# Sheet1.net
KiCad netlist of a schematic drawn in Altium Designer
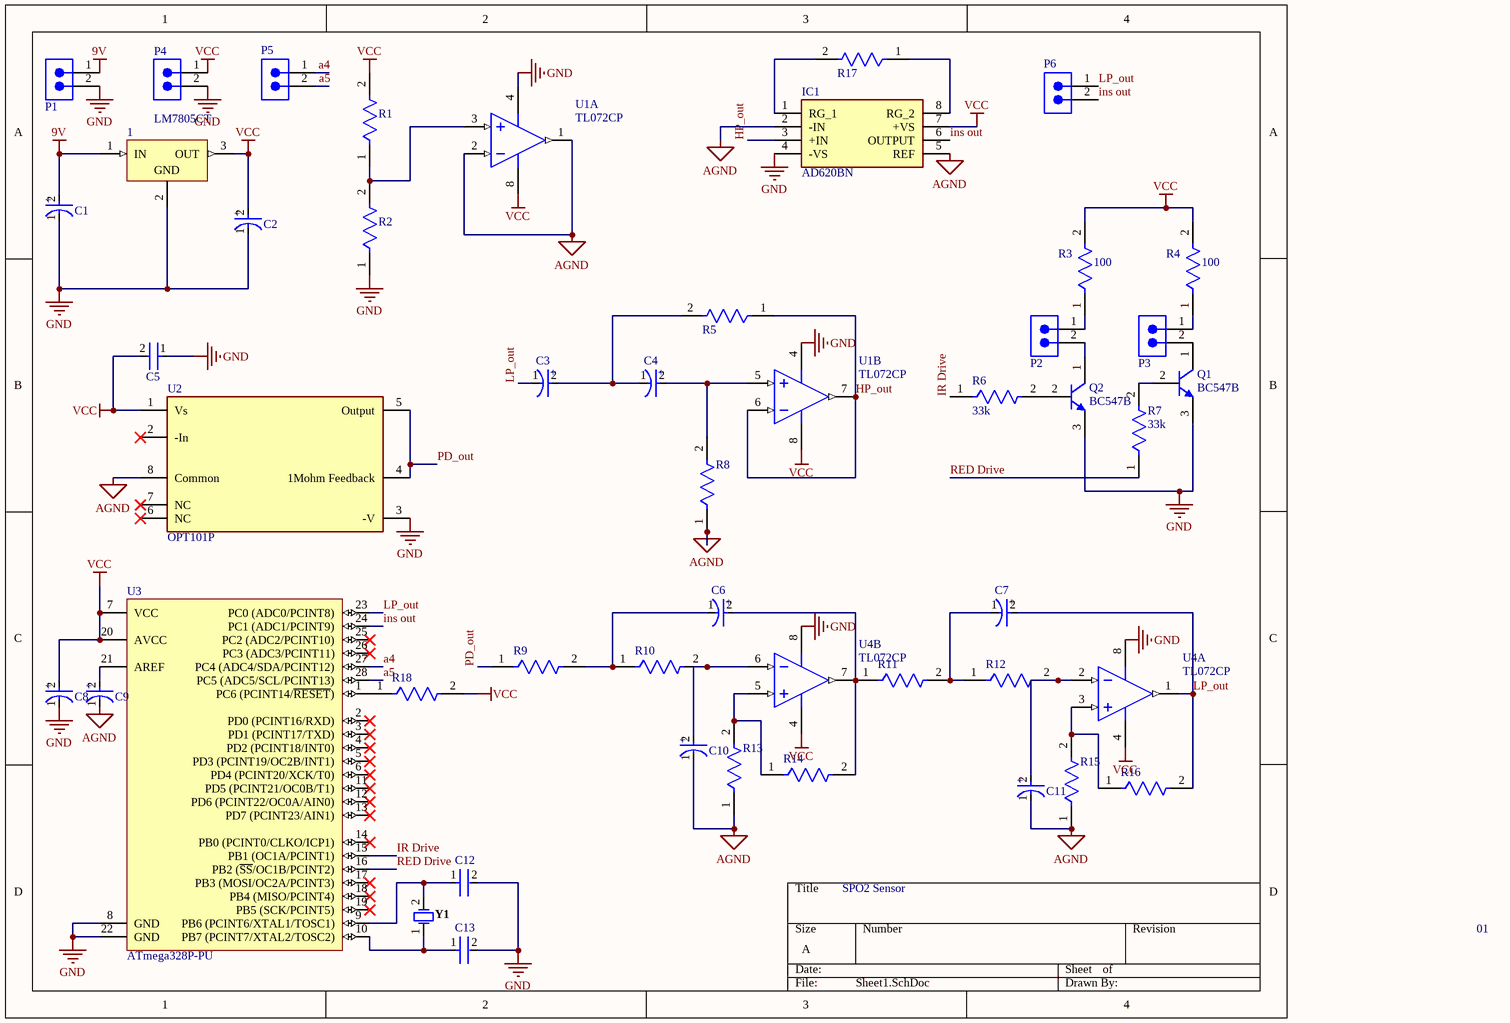
[diagram p0: Sheet1.SchDoc]

(export (version "E")
  (design (tool "Eeschema 10.0.6"))
  (components
    (comp (ref "1")
      (value "LM7805CT")
      (footprint "FAIR-TO-220-3")
      (description "Fixed Positive Standard Regulator, 5VBIPolar, PSFM3")
      (libsource (lib "herathhmsi 21") (part "FAIR-LM7805CT-TO220-3"))
    )
    (comp (ref "C1")
      (value "EEUFC1H150")
      (footprint "FP-RAD-TH-D_5_0_5-L_11_1-MFG")
      (description "Aluminum Electrolytic Capacitors (Radial Lead Type) AEC-Q200 Qualified 15uF ±20% 50V")
      (fields (field (name "TOLERANCE") "20%") (field (name "VOLTAGE") "50V"))
      (libsource (lib "Altium Content Vault") (part "a00bbbee19879c290e62620ae7e47b1"))
    )
    (comp (ref "C2")
      (value "EEUFC1H150")
      (footprint "FP-RAD-TH-D_5_0_5-L_11_1-MFG")
      (description "Aluminum Electrolytic Capacitors (Radial Lead Type) AEC-Q200 Qualified 15uF ±20% 50V")
      (fields (field (name "TOLERANCE") "20%") (field (name "VOLTAGE") "50V"))
      (libsource (lib "Altium Content Vault") (part "a00bbbee19879c290e62620ae7e47b1"))
    )
    (comp (ref "C3")
      (value "EEUFC1H150")
      (footprint "FP-RAD-TH-D_5_0_5-L_11_1-MFG")
      (description "Aluminum Electrolytic Capacitors (Radial Lead Type) AEC-Q200 Qualified 15uF ±20% 50V")
      (fields (field (name "TOLERANCE") "20%") (field (name "VOLTAGE") "50V"))
      (libsource (lib "Altium Content Vault") (part "a00bbbee19879c290e62620ae7e47b1"))
    )
    (comp (ref "C4")
      (value "EEUFC1H150")
      (footprint "FP-RAD-TH-D_5_0_5-L_11_1-MFG")
      (description "Aluminum Electrolytic Capacitors (Radial Lead Type) AEC-Q200 Qualified 15uF ±20% 50V")
      (fields (field (name "TOLERANCE") "20%") (field (name "VOLTAGE") "50V"))
      (libsource (lib "Altium Content Vault") (part "a00bbbee19879c290e62620ae7e47b1"))
    )
    (comp (ref "C5")
      (value "RCER72A104K1DBH03A")
      (footprint "FP-RCE1A2-MFG")
      (description "Cap Ceramic 100nF 100V X7R ±10% Radial 2.5mm +125°C Automotive Ammo Pack")
      (fields (field (name "TOLERANCE") "10%"))
      (libsource (lib "Altium Content Vault") (part "02cd4be3c70576c341d710602a673aa"))
    )
    (comp (ref "C6")
      (value "EEUFC1H150")
      (footprint "FP-RAD-TH-D_5_0_5-L_11_1-MFG")
      (description "Aluminum Electrolytic Capacitors (Radial Lead Type) AEC-Q200 Qualified 15uF ±20% 50V")
      (fields (field (name "TOLERANCE") "20%") (field (name "VOLTAGE") "50V"))
      (libsource (lib "Altium Content Vault") (part "a00bbbee19879c290e62620ae7e47b1"))
    )
    (comp (ref "C7")
      (value "EEUFC1H150")
      (footprint "FP-RAD-TH-D_5_0_5-L_11_1-MFG")
      (description "Aluminum Electrolytic Capacitors (Radial Lead Type) AEC-Q200 Qualified 15uF ±20% 50V")
      (fields (field (name "TOLERANCE") "20%") (field (name "VOLTAGE") "50V"))
      (libsource (lib "Altium Content Vault") (part "a00bbbee19879c290e62620ae7e47b1"))
    )
    (comp (ref "C8")
      (value "EEUFC1H150")
      (footprint "FP-RAD-TH-D_5_0_5-L_11_1-MFG")
      (description "Aluminum Electrolytic Capacitors (Radial Lead Type) AEC-Q200 Qualified 15uF ±20% 50V")
      (fields (field (name "TOLERANCE") "20%") (field (name "VOLTAGE") "50V"))
      (libsource (lib "Altium Content Vault") (part "a00bbbee19879c290e62620ae7e47b1"))
    )
    (comp (ref "C9")
      (value "EEUFC1H150")
      (footprint "FP-RAD-TH-D_5_0_5-L_11_1-MFG")
      (description "Aluminum Electrolytic Capacitors (Radial Lead Type) AEC-Q200 Qualified 15uF ±20% 50V")
      (fields (field (name "TOLERANCE") "20%") (field (name "VOLTAGE") "50V"))
      (libsource (lib "Altium Content Vault") (part "a00bbbee19879c290e62620ae7e47b1"))
    )
    (comp (ref "C10")
      (value "EEUFC1H150")
      (footprint "FP-RAD-TH-D_5_0_5-L_11_1-MFG")
      (description "Aluminum Electrolytic Capacitors (Radial Lead Type) AEC-Q200 Qualified 15uF ±20% 50V")
      (fields (field (name "TOLERANCE") "20%") (field (name "VOLTAGE") "50V"))
      (libsource (lib "Altium Content Vault") (part "a00bbbee19879c290e62620ae7e47b1"))
    )
    (comp (ref "C11")
      (value "EEUFC1H150")
      (footprint "FP-RAD-TH-D_5_0_5-L_11_1-MFG")
      (description "Aluminum Electrolytic Capacitors (Radial Lead Type) AEC-Q200 Qualified 15uF ±20% 50V")
      (fields (field (name "TOLERANCE") "20%") (field (name "VOLTAGE") "50V"))
      (libsource (lib "Altium Content Vault") (part "a00bbbee19879c290e62620ae7e47b1"))
    )
    (comp (ref "C12")
      (value "RCE5C2A102J0K1H03B")
      (footprint "FP-RCE0K1-MFG")
      (description "Cap Ceramic 1nF 100V C0G ±5% Radial 5mm +125°C Automotive Bulk")
      (fields (field (name "TOLERANCE") "5%"))
      (libsource (lib "Altium Content Vault") (part "b4654b650e69147ec39a6b967a45e02"))
    )
    (comp (ref "C13")
      (value "RCE5C2A102J0K1H03B")
      (footprint "FP-RCE0K1-MFG")
      (description "Cap Ceramic 1nF 100V C0G ±5% Radial 5mm +125°C Automotive Bulk")
      (fields (field (name "TOLERANCE") "5%"))
      (libsource (lib "Altium Content Vault") (part "b4654b650e69147ec39a6b967a45e02"))
    )
    (comp (ref "IC1")
      (value "AD620BN")
      (footprint "DIP794W56P254L959H533Q8N")
      (description "Integrated Circuit")
      (libsource (lib "Schlib1") (part "AD620BN"))
    )
    (comp (ref "P1")
      (value "TSW-102-26-F-S")
      (footprint "SMTC-TSW-102-26-XX-S")
      (description "0.025\" SQ Post Header, Through-hole, Vertical, -55 to 125 degC, 2.54 mm Pitch, 2-Pin, Male, RoHS")
      (fields (field (name "MANUFACTURER") "Samtec"))
      (libsource (lib "Altium Content Vault") (part "SMTC-TSW-102-X-X-S-X"))
    )
    (comp (ref "P2")
      (value "TSW-102-26-F-S")
      (footprint "SMTC-TSW-102-26-XX-S")
      (description "0.025\" SQ Post Header, Through-hole, Vertical, -55 to 125 degC, 2.54 mm Pitch, 2-Pin, Male, RoHS")
      (fields (field (name "MANUFACTURER") "Samtec"))
      (libsource (lib "Altium Content Vault") (part "SMTC-TSW-102-X-X-S-X"))
    )
    (comp (ref "P3")
      (value "TSW-102-26-F-S")
      (footprint "SMTC-TSW-102-26-XX-S")
      (description "0.025\" SQ Post Header, Through-hole, Vertical, -55 to 125 degC, 2.54 mm Pitch, 2-Pin, Male, RoHS")
      (fields (field (name "MANUFACTURER") "Samtec"))
      (libsource (lib "Altium Content Vault") (part "SMTC-TSW-102-X-X-S-X"))
    )
    (comp (ref "P4")
      (value "TSW-102-26-F-S")
      (footprint "SMTC-TSW-102-26-XX-S")
      (description "0.025\" SQ Post Header, Through-hole, Vertical, -55 to 125 degC, 2.54 mm Pitch, 2-Pin, Male, RoHS")
      (fields (field (name "MANUFACTURER") "Samtec"))
      (libsource (lib "Altium Content Vault") (part "SMTC-TSW-102-X-X-S-X"))
    )
    (comp (ref "P5")
      (value "TSW-102-26-F-S")
      (footprint "SMTC-TSW-102-26-XX-S")
      (description "0.025\" SQ Post Header, Through-hole, Vertical, -55 to 125 degC, 2.54 mm Pitch, 2-Pin, Male, RoHS")
      (fields (field (name "MANUFACTURER") "Samtec"))
      (libsource (lib "Altium Content Vault") (part "SMTC-TSW-102-X-X-S-X"))
    )
    (comp (ref "P6")
      (value "TSW-102-26-F-S")
      (footprint "SMTC-TSW-102-26-XX-S")
      (description "0.025\" SQ Post Header, Through-hole, Vertical, -55 to 125 degC, 2.54 mm Pitch, 2-Pin, Male, RoHS")
      (fields (field (name "MANUFACTURER") "Samtec"))
      (libsource (lib "Altium Content Vault") (part "SMTC-TSW-102-X-X-S-X"))
    )
    (comp (ref "Q1")
      (value "BC547B")
      (footprint "ONSC-TO-92-3-29-11")
      (description "Amplifier Transistor, NPN Silicon, 3-Pin TO-92, Bulk Box")
      (fields (field (name "MANUFACTURER") "On Semiconductor"))
      (libsource (lib "Altium Content Vault") (part "ONSC-NPN-C1B2E3-3"))
    )
    (comp (ref "Q2")
      (value "BC547B")
      (footprint "ONSC-TO-92-3-29-11")
      (description "Amplifier Transistor, NPN Silicon, 3-Pin TO-92, Bulk Box")
      (fields (field (name "MANUFACTURER") "On Semiconductor"))
      (libsource (lib "Altium Content Vault") (part "ONSC-NPN-C1B2E3-3"))
    )
    (comp (ref "R1")
      (value "RLR07C1002FSB14")
      (footprint "FP-RLR07-MFG")
      (fields (field (name "TOLERANCE") "1%"))
      (libsource (lib "Altium Content Vault") (part "1029c3af85768c4190bb7ad29bc67b5"))
    )
    (comp (ref "R2")
      (value "RLR07C1002FSB14")
      (footprint "FP-RLR07-MFG")
      (fields (field (name "TOLERANCE") "1%"))
      (libsource (lib "Altium Content Vault") (part "1029c3af85768c4190bb7ad29bc67b5"))
    )
    (comp (ref "R3")
      (value "100")
      (footprint "FP-RLR07-MFG")
      (fields (field (name "TOLERANCE") "1%"))
      (libsource (lib "Altium Content Vault") (part "1029c3af85768c4190bb7ad29bc67b5"))
    )
    (comp (ref "R4")
      (value "100")
      (footprint "FP-RLR07-MFG")
      (fields (field (name "TOLERANCE") "1%"))
      (libsource (lib "Altium Content Vault") (part "1029c3af85768c4190bb7ad29bc67b5"))
    )
    (comp (ref "R5")
      (value "RLR07C1002FSB14")
      (footprint "FP-RLR07-MFG")
      (fields (field (name "TOLERANCE") "1%"))
      (libsource (lib "Altium Content Vault") (part "1029c3af85768c4190bb7ad29bc67b5"))
    )
    (comp (ref "R6")
      (value "33k")
      (footprint "FP-RLR07-MFG")
      (fields (field (name "TOLERANCE") "1%"))
      (libsource (lib "Altium Content Vault") (part "1029c3af85768c4190bb7ad29bc67b5"))
    )
    (comp (ref "R7")
      (value "33k")
      (footprint "FP-RLR07-MFG")
      (fields (field (name "TOLERANCE") "1%"))
      (libsource (lib "Altium Content Vault") (part "1029c3af85768c4190bb7ad29bc67b5"))
    )
    (comp (ref "R8")
      (value "RLR07C1002FSB14")
      (footprint "FP-RLR07-MFG")
      (fields (field (name "TOLERANCE") "1%"))
      (libsource (lib "Altium Content Vault") (part "1029c3af85768c4190bb7ad29bc67b5"))
    )
    (comp (ref "R9")
      (value "RLR07C1002FSB14")
      (footprint "FP-RLR07-MFG")
      (fields (field (name "TOLERANCE") "1%"))
      (libsource (lib "Altium Content Vault") (part "1029c3af85768c4190bb7ad29bc67b5"))
    )
    (comp (ref "R10")
      (value "RLR07C1002FSB14")
      (footprint "FP-RLR07-MFG")
      (fields (field (name "TOLERANCE") "1%"))
      (libsource (lib "Altium Content Vault") (part "1029c3af85768c4190bb7ad29bc67b5"))
    )
    (comp (ref "R11")
      (value "RLR07C1002FSB14")
      (footprint "FP-RLR07-MFG")
      (fields (field (name "TOLERANCE") "1%"))
      (libsource (lib "Altium Content Vault") (part "1029c3af85768c4190bb7ad29bc67b5"))
    )
    (comp (ref "R12")
      (value "RLR07C1002FSB14")
      (footprint "FP-RLR07-MFG")
      (fields (field (name "TOLERANCE") "1%"))
      (libsource (lib "Altium Content Vault") (part "1029c3af85768c4190bb7ad29bc67b5"))
    )
    (comp (ref "R13")
      (value "RLR07C1002FSB14")
      (footprint "FP-RLR07-MFG")
      (fields (field (name "TOLERANCE") "1%"))
      (libsource (lib "Altium Content Vault") (part "1029c3af85768c4190bb7ad29bc67b5"))
    )
    (comp (ref "R14")
      (value "RLR07C1002FSB14")
      (footprint "FP-RLR07-MFG")
      (fields (field (name "TOLERANCE") "1%"))
      (libsource (lib "Altium Content Vault") (part "1029c3af85768c4190bb7ad29bc67b5"))
    )
    (comp (ref "R15")
      (value "RLR07C1002FSB14")
      (footprint "FP-RLR07-MFG")
      (fields (field (name "TOLERANCE") "1%"))
      (libsource (lib "Altium Content Vault") (part "1029c3af85768c4190bb7ad29bc67b5"))
    )
    (comp (ref "R16")
      (value "RLR07C1002FSB14")
      (footprint "FP-RLR07-MFG")
      (fields (field (name "TOLERANCE") "1%"))
      (libsource (lib "Altium Content Vault") (part "1029c3af85768c4190bb7ad29bc67b5"))
    )
    (comp (ref "R17")
      (value "RLR07C1002FSB14")
      (footprint "FP-RLR07-MFG")
      (fields (field (name "TOLERANCE") "1%"))
      (libsource (lib "Altium Content Vault") (part "1029c3af85768c4190bb7ad29bc67b5"))
    )
    (comp (ref "R18")
      (value "RLR07C1002FSB14")
      (footprint "FP-RLR07-MFG")
      (fields (field (name "TOLERANCE") "1%"))
      (libsource (lib "Altium Content Vault") (part "1029c3af85768c4190bb7ad29bc67b5"))
    )
    (comp (ref "U1")
      (value "TL072CP")
      (footprint "P0008A")
      (fields (field (name "MANUFACTURER") "Texas Instruments"))
      (libsource (lib "Altium Content Vault") (part "TI-AMP-D6-2-8_D"))
    )
    (comp (ref "U2")
      (value "OPT101P")
      (footprint "FP-NTC0008A-MFG")
      (description "SENSOR OPT 650NM AMBIENT 8DIP")
      (libsource (lib "Altium Content Vault") (part "30f9e53383154c6943bb97ca6fc90e9"))
    )
    (comp (ref "U3")
      (value "ATmega328P-PU")
      (footprint "28P3")
      (libsource (lib "Altium Content Vault") (part "MC-8B-ATM48-IL28"))
    )
    (comp (ref "U4")
      (value "TL072CP")
      (footprint "P0008A")
      (fields (field (name "MANUFACTURER") "Texas Instruments"))
      (libsource (lib "Altium Content Vault") (part "TI-AMP-D6-2-8_D"))
    )
    (comp (ref "Y1")
      (value "FOXSLF/160-20")
      (footprint "FOX-FOXSLF160-20")
      (description "Resistance Weld Thru-Hole Crystal, 16 MHz, -20 to 70 degC, 2-Pin THD, RoHS, Bulk")
      (fields (field (name "TOLERANCE") "1%"))
      (libsource (lib "Altium Content Vault") (part "XTAL-1-2-2"))
    )
  )
  (nets
    (net (code "1") (name "/HP_out") (class "Default")
      (node (ref "IC1") (pin "3") (pinfunction "+IN_3") (pintype "passive"))
      (node (ref "R5") (pin "1") (pinfunction "1_1") (pintype "passive"))
      (node (ref "U1") (pin "6") (pinfunction "IN2-_6") (pintype "input"))
      (node (ref "U1") (pin "7") (pinfunction "OUT2_7") (pintype "output"))
    )
    (net (code "2") (name "/IR Drive") (class "Default")
      (node (ref "R6") (pin "1") (pinfunction "1_1") (pintype "passive"))
      (node (ref "U3") (pin "15") (pinfunction "PB1_(OC1A/PCINT1)_15") (pintype "bidirectional"))
    )
    (net (code "3") (name "/LP_out") (class "Default")
      (node (ref "C3") (pin "1") (pinfunction "C_1") (pintype "passive"))
      (node (ref "C7") (pin "2") (pinfunction "A_2") (pintype "passive"))
      (node (ref "P6") (pin "1") (pinfunction "1_1") (pintype "passive"))
      (node (ref "R16") (pin "2") (pinfunction "2_2") (pintype "passive"))
      (node (ref "U3") (pin "23") (pinfunction "PC0_(ADC0/PCINT8)_23") (pintype "bidirectional"))
      (node (ref "U4") (pin "1") (pinfunction "OUT1_1") (pintype "output"))
    )
    (net (code "4") (name "/PD_out") (class "Default")
      (node (ref "R9") (pin "1") (pinfunction "1_1") (pintype "passive"))
      (node (ref "U2") (pin "4") (pinfunction "1Mohm_Feedback_4") (pintype "passive"))
      (node (ref "U2") (pin "5") (pinfunction "Output_5") (pintype "passive"))
    )
    (net (code "5") (name "/RED Drive") (class "Default")
      (node (ref "R7") (pin "1") (pinfunction "1_1") (pintype "passive"))
      (node (ref "U3") (pin "16") (pinfunction "PB2_(~{SS}/OC1B/PCINT2)_16") (pintype "bidirectional"))
    )
    (net (code "6") (name "/a4") (class "Default")
      (node (ref "P5") (pin "1") (pinfunction "1_1") (pintype "passive"))
      (node (ref "U3") (pin "27") (pinfunction "PC4_(ADC4/SDA/PCINT12)_27") (pintype "bidirectional"))
    )
    (net (code "7") (name "/a5") (class "Default")
      (node (ref "P5") (pin "2") (pinfunction "2_2") (pintype "passive"))
      (node (ref "U3") (pin "28") (pinfunction "PC5_(ADC5/SCL/PCINT13)_28") (pintype "bidirectional"))
    )
    (net (code "8") (name "/ins out") (class "Default")
      (node (ref "IC1") (pin "6") (pinfunction "OUTPUT_6") (pintype "passive"))
      (node (ref "P6") (pin "2") (pinfunction "2_2") (pintype "passive"))
      (node (ref "U3") (pin "24") (pinfunction "PC1_(ADC1/PCINT9)_24") (pintype "bidirectional"))
    )
    (net (code "9") (name "9V") (class "Default")
      (node (ref "1") (pin "1") (pinfunction "IN_1") (pintype "input"))
      (node (ref "C1") (pin "2") (pinfunction "A_2") (pintype "passive"))
      (node (ref "P1") (pin "1") (pinfunction "1_1") (pintype "passive"))
    )
    (net (code "10") (name "AGND") (class "Default")
      (node (ref "C10") (pin "1") (pinfunction "C_1") (pintype "passive"))
      (node (ref "C11") (pin "1") (pinfunction "C_1") (pintype "passive"))
      (node (ref "C9") (pin "1") (pinfunction "C_1") (pintype "passive"))
      (node (ref "IC1") (pin "2") (pinfunction "-IN_2") (pintype "passive"))
      (node (ref "IC1") (pin "5") (pinfunction "REF_5") (pintype "passive"))
      (node (ref "R13") (pin "1") (pinfunction "1_1") (pintype "passive"))
      (node (ref "R15") (pin "1") (pinfunction "1_1") (pintype "passive"))
      (node (ref "R8") (pin "1") (pinfunction "1_1") (pintype "passive"))
      (node (ref "U1") (pin "1") (pinfunction "OUT1_1") (pintype "output"))
      (node (ref "U1") (pin "2") (pinfunction "IN1-_2") (pintype "input"))
      (node (ref "U2") (pin "8") (pinfunction "Common_8") (pintype "passive"))
    )
    (net (code "11") (name "GND") (class "Default")
      (node (ref "1") (pin "2") (pinfunction "GND_2") (pintype "power_in"))
      (node (ref "C1") (pin "1") (pinfunction "C_1") (pintype "passive"))
      (node (ref "C12") (pin "2") (pinfunction "2_2") (pintype "passive"))
      (node (ref "C13") (pin "2") (pinfunction "2_2") (pintype "passive"))
      (node (ref "C2") (pin "1") (pinfunction "C_1") (pintype "passive"))
      (node (ref "C5") (pin "1") (pinfunction "1_1") (pintype "passive"))
      (node (ref "C8") (pin "1") (pinfunction "C_1") (pintype "passive"))
      (node (ref "IC1") (pin "4") (pinfunction "-VS_4") (pintype "passive"))
      (node (ref "P1") (pin "2") (pinfunction "2_2") (pintype "passive"))
      (node (ref "P4") (pin "2") (pinfunction "2_2") (pintype "passive"))
      (node (ref "Q1") (pin "3") (pinfunction "E_3") (pintype "passive"))
      (node (ref "Q2") (pin "3") (pinfunction "E_3") (pintype "passive"))
      (node (ref "R2") (pin "1") (pinfunction "1_1") (pintype "passive"))
      (node (ref "U1") (pin "4") (pinfunction "VCC-_4") (pintype "power_in"))
      (node (ref "U2") (pin "3") (pinfunction "-V_3") (pintype "power_in"))
      (node (ref "U3") (pin "22") (pinfunction "GND_22") (pintype "power_in"))
      (node (ref "U3") (pin "8") (pinfunction "GND_8") (pintype "power_in"))
      (node (ref "U4") (pin "8") (pinfunction "VCC+_8") (pintype "power_in"))
    )
    (net (code "12") (name "Net-(C3-A)") (class "Default")
      (node (ref "C3") (pin "2") (pinfunction "A_2") (pintype "passive"))
      (node (ref "C4") (pin "1") (pinfunction "C_1") (pintype "passive"))
      (node (ref "R5") (pin "2") (pinfunction "2_2") (pintype "passive"))
    )
    (net (code "13") (name "Net-(C4-A)") (class "Default")
      (node (ref "C4") (pin "2") (pinfunction "A_2") (pintype "passive"))
      (node (ref "R8") (pin "2") (pinfunction "2_2") (pintype "passive"))
      (node (ref "U1") (pin "5") (pinfunction "IN2+_5") (pintype "input"))
    )
    (net (code "14") (name "Net-(C6-A)") (class "Default")
      (node (ref "C6") (pin "2") (pinfunction "A_2") (pintype "passive"))
      (node (ref "R11") (pin "1") (pinfunction "1_1") (pintype "passive"))
      (node (ref "R14") (pin "2") (pinfunction "2_2") (pintype "passive"))
      (node (ref "U4") (pin "7") (pinfunction "OUT2_7") (pintype "output"))
    )
    (net (code "15") (name "Net-(C6-C)") (class "Default")
      (node (ref "C6") (pin "1") (pinfunction "C_1") (pintype "passive"))
      (node (ref "R10") (pin "1") (pinfunction "1_1") (pintype "passive"))
      (node (ref "R9") (pin "2") (pinfunction "2_2") (pintype "passive"))
    )
    (net (code "16") (name "Net-(C7-C)") (class "Default")
      (node (ref "C7") (pin "1") (pinfunction "C_1") (pintype "passive"))
      (node (ref "R11") (pin "2") (pinfunction "2_2") (pintype "passive"))
      (node (ref "R12") (pin "1") (pinfunction "1_1") (pintype "passive"))
    )
    (net (code "17") (name "Net-(C9-A)") (class "Default")
      (node (ref "C9") (pin "2") (pinfunction "A_2") (pintype "passive"))
      (node (ref "U3") (pin "21") (pinfunction "AREF_21") (pintype "power_in"))
    )
    (net (code "18") (name "Net-(C10-A)") (class "Default")
      (node (ref "C10") (pin "2") (pinfunction "A_2") (pintype "passive"))
      (node (ref "R10") (pin "2") (pinfunction "2_2") (pintype "passive"))
      (node (ref "U4") (pin "6") (pinfunction "IN2-_6") (pintype "input"))
    )
    (net (code "19") (name "Net-(C11-A)") (class "Default")
      (node (ref "C11") (pin "2") (pinfunction "A_2") (pintype "passive"))
      (node (ref "R12") (pin "2") (pinfunction "2_2") (pintype "passive"))
      (node (ref "U4") (pin "2") (pinfunction "IN1-_2") (pintype "input"))
    )
    (net (code "20") (name "Net-(IC1-RG_1)") (class "Default")
      (node (ref "IC1") (pin "1") (pinfunction "RG_1_1") (pintype "passive"))
      (node (ref "R17") (pin "2") (pinfunction "2_2") (pintype "passive"))
    )
    (net (code "21") (name "Net-(IC1-RG_2)") (class "Default")
      (node (ref "IC1") (pin "8") (pinfunction "RG_2_8") (pintype "passive"))
      (node (ref "R17") (pin "1") (pinfunction "1_1") (pintype "passive"))
    )
    (net (code "22") (name "Net-(P2-Pad1)") (class "Default")
      (node (ref "P2") (pin "1") (pinfunction "1_1") (pintype "passive"))
      (node (ref "R3") (pin "1") (pinfunction "1_1") (pintype "passive"))
    )
    (net (code "23") (name "Net-(P3-Pad1)") (class "Default")
      (node (ref "P3") (pin "1") (pinfunction "1_1") (pintype "passive"))
      (node (ref "R4") (pin "1") (pinfunction "1_1") (pintype "passive"))
    )
    (net (code "24") (name "Net-(Q1-B)") (class "Default")
      (node (ref "Q1") (pin "2") (pinfunction "B_2") (pintype "passive"))
      (node (ref "R7") (pin "2") (pinfunction "2_2") (pintype "passive"))
    )
    (net (code "25") (name "Net-(Q1-C)") (class "Default")
      (node (ref "P3") (pin "2") (pinfunction "2_2") (pintype "passive"))
      (node (ref "Q1") (pin "1") (pinfunction "C_1") (pintype "passive"))
    )
    (net (code "26") (name "Net-(Q2-B)") (class "Default")
      (node (ref "Q2") (pin "2") (pinfunction "B_2") (pintype "passive"))
      (node (ref "R6") (pin "2") (pinfunction "2_2") (pintype "passive"))
    )
    (net (code "27") (name "Net-(Q2-C)") (class "Default")
      (node (ref "P2") (pin "2") (pinfunction "2_2") (pintype "passive"))
      (node (ref "Q2") (pin "1") (pinfunction "C_1") (pintype "passive"))
    )
    (net (code "28") (name "Net-(U1A-IN1+)") (class "Default")
      (node (ref "R1") (pin "1") (pinfunction "1_1") (pintype "passive"))
      (node (ref "R2") (pin "2") (pinfunction "2_2") (pintype "passive"))
      (node (ref "U1") (pin "3") (pinfunction "IN1+_3") (pintype "input"))
    )
    (net (code "29") (name "Net-(U3-PB6_(PCINT6{slash}XTAL1{slash}TOSC1))") (class "Default")
      (node (ref "C12") (pin "1") (pinfunction "1_1") (pintype "passive"))
      (node (ref "U3") (pin "9") (pinfunction "PB6_(PCINT6/XTAL1/TOSC1)_9") (pintype "bidirectional"))
      (node (ref "Y1") (pin "2") (pinfunction "2_2") (pintype "passive"))
    )
    (net (code "30") (name "Net-(U3-PB7_(PCINT7{slash}XTAL2{slash}TOSC2))") (class "Default")
      (node (ref "C13") (pin "1") (pinfunction "1_1") (pintype "passive"))
      (node (ref "U3") (pin "10") (pinfunction "PB7_(PCINT7/XTAL2/TOSC2)_10") (pintype "bidirectional"))
      (node (ref "Y1") (pin "1") (pinfunction "1_1") (pintype "passive"))
    )
    (net (code "31") (name "Net-(U3-PC6_(PCINT14{slash}~{RESET}))") (class "Default")
      (node (ref "R18") (pin "1") (pinfunction "1_1") (pintype "passive"))
      (node (ref "U3") (pin "1") (pinfunction "PC6_(PCINT14/~{RESET})_1") (pintype "bidirectional"))
    )
    (net (code "32") (name "Net-(U4A-IN1+)") (class "Default")
      (node (ref "R15") (pin "2") (pinfunction "2_2") (pintype "passive"))
      (node (ref "R16") (pin "1") (pinfunction "1_1") (pintype "passive"))
      (node (ref "U4") (pin "3") (pinfunction "IN1+_3") (pintype "input"))
    )
    (net (code "33") (name "Net-(U4B-IN2+)") (class "Default")
      (node (ref "R13") (pin "2") (pinfunction "2_2") (pintype "passive"))
      (node (ref "R14") (pin "1") (pinfunction "1_1") (pintype "passive"))
      (node (ref "U4") (pin "5") (pinfunction "IN2+_5") (pintype "input"))
    )
    (net (code "34") (name "VCC") (class "Default")
      (node (ref "1") (pin "3") (pinfunction "OUT_3") (pintype "output"))
      (node (ref "C2") (pin "2") (pinfunction "A_2") (pintype "passive"))
      (node (ref "C5") (pin "2") (pinfunction "2_2") (pintype "passive"))
      (node (ref "C8") (pin "2") (pinfunction "A_2") (pintype "passive"))
      (node (ref "IC1") (pin "7") (pinfunction "+VS_7") (pintype "passive"))
      (node (ref "P4") (pin "1") (pinfunction "1_1") (pintype "passive"))
      (node (ref "R1") (pin "2") (pinfunction "2_2") (pintype "passive"))
      (node (ref "R18") (pin "2") (pinfunction "2_2") (pintype "passive"))
      (node (ref "R3") (pin "2") (pinfunction "2_2") (pintype "passive"))
      (node (ref "R4") (pin "2") (pinfunction "2_2") (pintype "passive"))
      (node (ref "U1") (pin "8") (pinfunction "VCC+_8") (pintype "power_in"))
      (node (ref "U2") (pin "1") (pinfunction "Vs_1") (pintype "power_in"))
      (node (ref "U3") (pin "20") (pinfunction "AVCC_20") (pintype "power_in"))
      (node (ref "U3") (pin "7") (pinfunction "VCC_7") (pintype "power_in"))
      (node (ref "U4") (pin "4") (pinfunction "VCC-_4") (pintype "power_in"))
    )
    (net (code "35") (name "unconnected-(U2--In-Pad2)") (class "Default")
      (node (ref "U2") (pin "2") (pinfunction "-In_2") (pintype "power_in+no_connect"))
    )
    (net (code "36") (name "unconnected-(U2-NC-Pad6)") (class "Default")
      (node (ref "U2") (pin "6") (pinfunction "NC_6") (pintype "passive+no_connect"))
    )
    (net (code "37") (name "unconnected-(U2-NC-Pad7)") (class "Default")
      (node (ref "U2") (pin "7") (pinfunction "NC_7") (pintype "passive+no_connect"))
    )
    (net (code "38") (name "unconnected-(U3-PB0_(PCINT0{slash}CLKO{slash}ICP1)-Pad14)") (class "Default")
      (node (ref "U3") (pin "14") (pinfunction "PB0_(PCINT0/CLKO/ICP1)_14") (pintype "bidirectional+no_connect"))
    )
    (net (code "39") (name "unconnected-(U3-PB3_(MOSI{slash}OC2A{slash}PCINT3)-Pad17)") (class "Default")
      (node (ref "U3") (pin "17") (pinfunction "PB3_(MOSI/OC2A/PCINT3)_17") (pintype "bidirectional+no_connect"))
    )
    (net (code "40") (name "unconnected-(U3-PB4_(MISO{slash}PCINT4)-Pad18)") (class "Default")
      (node (ref "U3") (pin "18") (pinfunction "PB4_(MISO/PCINT4)_18") (pintype "bidirectional+no_connect"))
    )
    (net (code "41") (name "unconnected-(U3-PB5_(SCK{slash}PCINT5)-Pad19)") (class "Default")
      (node (ref "U3") (pin "19") (pinfunction "PB5_(SCK/PCINT5)_19") (pintype "bidirectional+no_connect"))
    )
    (net (code "42") (name "unconnected-(U3-PC2_(ADC2{slash}PCINT10)-Pad25)") (class "Default")
      (node (ref "U3") (pin "25") (pinfunction "PC2_(ADC2/PCINT10)_25") (pintype "bidirectional+no_connect"))
    )
    (net (code "43") (name "unconnected-(U3-PC3_(ADC3{slash}PCINT11)-Pad26)") (class "Default")
      (node (ref "U3") (pin "26") (pinfunction "PC3_(ADC3/PCINT11)_26") (pintype "bidirectional+no_connect"))
    )
    (net (code "44") (name "unconnected-(U3-PD0_(PCINT16{slash}RXD)-Pad2)") (class "Default")
      (node (ref "U3") (pin "2") (pinfunction "PD0_(PCINT16/RXD)_2") (pintype "bidirectional+no_connect"))
    )
    (net (code "45") (name "unconnected-(U3-PD1_(PCINT17{slash}TXD)-Pad3)") (class "Default")
      (node (ref "U3") (pin "3") (pinfunction "PD1_(PCINT17/TXD)_3") (pintype "bidirectional+no_connect"))
    )
    (net (code "46") (name "unconnected-(U3-PD2_(PCINT18{slash}INT0)-Pad4)") (class "Default")
      (node (ref "U3") (pin "4") (pinfunction "PD2_(PCINT18/INT0)_4") (pintype "bidirectional+no_connect"))
    )
    (net (code "47") (name "unconnected-(U3-PD3_(PCINT19{slash}OC2B{slash}INT1)-Pad5)") (class "Default")
      (node (ref "U3") (pin "5") (pinfunction "PD3_(PCINT19/OC2B/INT1)_5") (pintype "bidirectional+no_connect"))
    )
    (net (code "48") (name "unconnected-(U3-PD4_(PCINT20{slash}XCK{slash}T0)-Pad6)") (class "Default")
      (node (ref "U3") (pin "6") (pinfunction "PD4_(PCINT20/XCK/T0)_6") (pintype "bidirectional+no_connect"))
    )
    (net (code "49") (name "unconnected-(U3-PD5_(PCINT21{slash}OC0B{slash}T1)-Pad11)") (class "Default")
      (node (ref "U3") (pin "11") (pinfunction "PD5_(PCINT21/OC0B/T1)_11") (pintype "bidirectional+no_connect"))
    )
    (net (code "50") (name "unconnected-(U3-PD6_(PCINT22{slash}OC0A{slash}AIN0)-Pad12)") (class "Default")
      (node (ref "U3") (pin "12") (pinfunction "PD6_(PCINT22/OC0A/AIN0)_12") (pintype "bidirectional+no_connect"))
    )
    (net (code "51") (name "unconnected-(U3-PD7_(PCINT23{slash}AIN1)-Pad13)") (class "Default")
      (node (ref "U3") (pin "13") (pinfunction "PD7_(PCINT23/AIN1)_13") (pintype "bidirectional+no_connect"))
    )
  )
)
